# TriMod_Adapter_CPLD_Version.net
KiCad netlist of a schematic drawn in Altium Designer
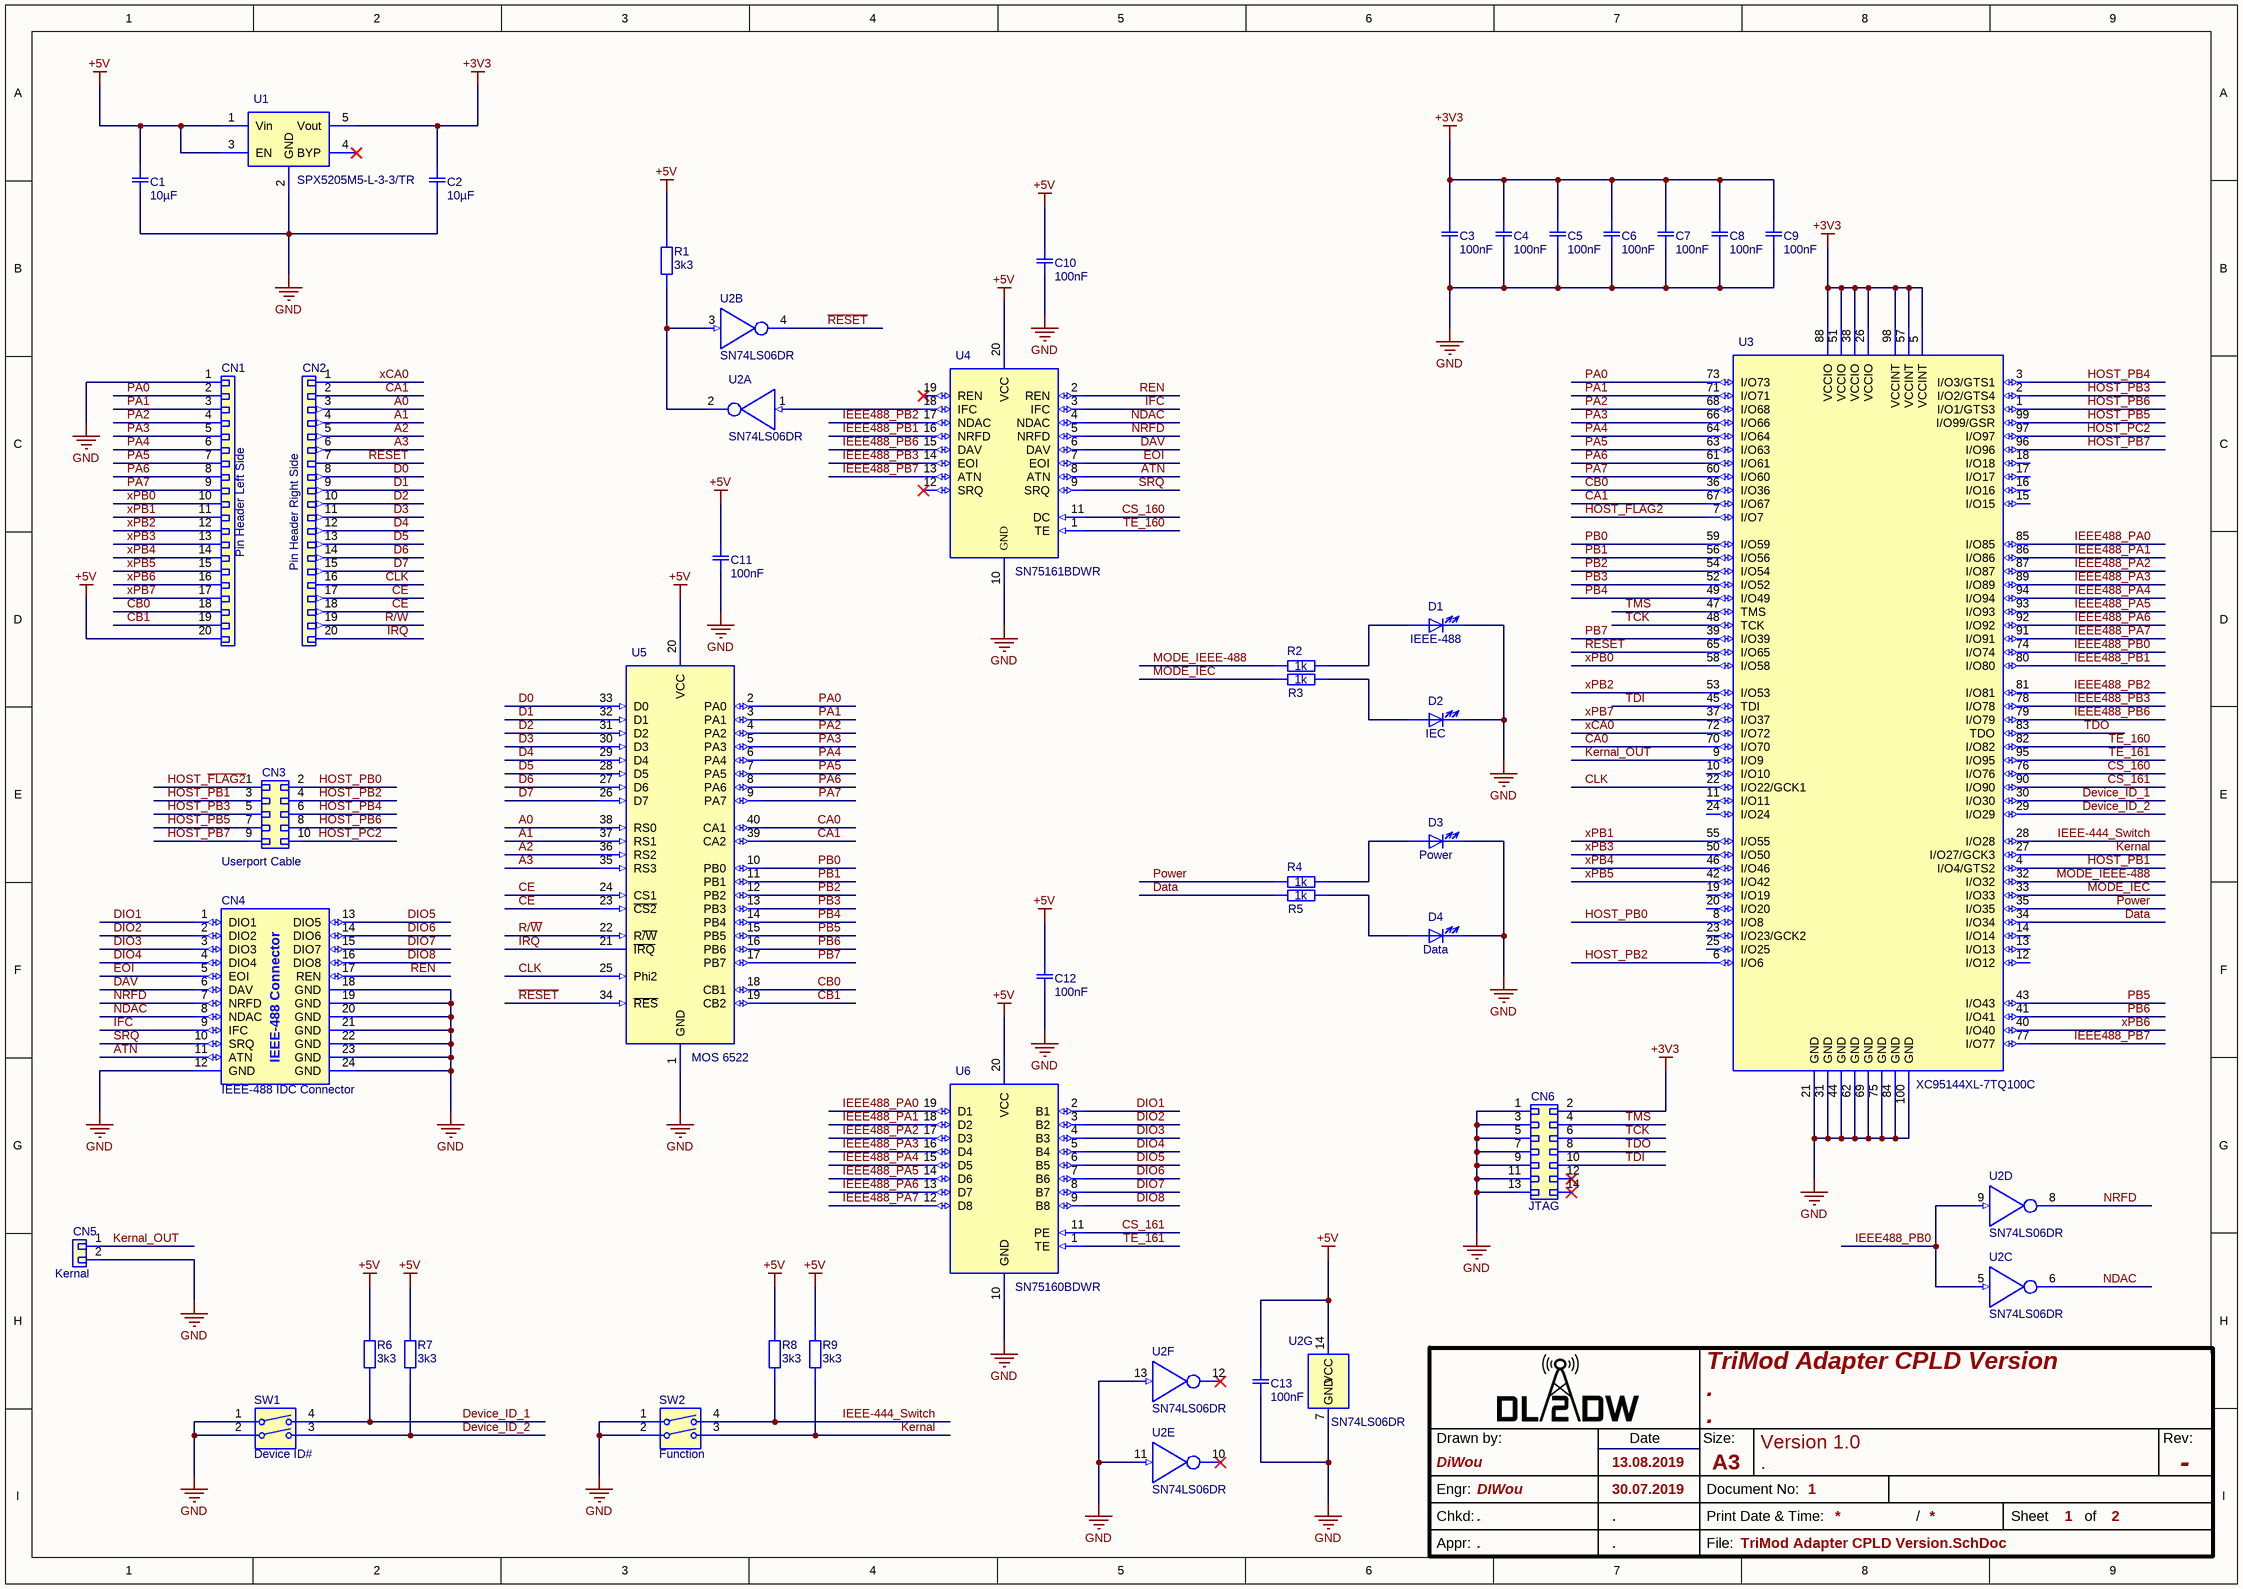
[diagram p0: TriMod Adapter CPLD Version.SchDoc]

(export (version "E")
  (design (tool "Eeschema 10.0.6"))
  (components
    (comp (ref "C1")
      (value "10µF")
      (footprint "Kemet C0805CxxxK8RACTU Series H=1.4mm")
      (description "KEMET - C0805C106K8RACTU - CAP, 10µF, 10V, 10%, X7R, 0805")
      (fields (field (name "VOLTAGE") "10V") (field (name "TOLERANCE") "10%"))
      (libsource (lib "PCB-Tech Cloud") (part "Capacitor"))
    )
    (comp (ref "C2")
      (value "10µF")
      (footprint "Kemet C0805CxxxK8RACTU Series H=1.4mm")
      (description "KEMET - C0805C106K8RACTU - CAP, 10µF, 10V, 10%, X7R, 0805")
      (fields (field (name "VOLTAGE") "10V") (field (name "TOLERANCE") "10%"))
      (libsource (lib "PCB-Tech Cloud") (part "Capacitor"))
    )
    (comp (ref "C3")
      (value "100nF")
      (footprint "CAP 100nF SMD 0603 C0603C104J3RACTU")
      (fields (field (name "TOLERANCE") "5%") (field (name "VOLTAGE") "25V"))
      (libsource (lib "PCB-Tech Cloud") (part "Capacitor"))
    )
    (comp (ref "C4")
      (value "100nF")
      (footprint "CAP 100nF SMD 0603 C0603C104J3RACTU")
      (fields (field (name "TOLERANCE") "5%") (field (name "VOLTAGE") "25V"))
      (libsource (lib "PCB-Tech Cloud") (part "Capacitor"))
    )
    (comp (ref "C5")
      (value "100nF")
      (footprint "CAP 100nF SMD 0603 C0603C104J3RACTU")
      (fields (field (name "TOLERANCE") "5%") (field (name "VOLTAGE") "25V"))
      (libsource (lib "PCB-Tech Cloud") (part "Capacitor"))
    )
    (comp (ref "C6")
      (value "100nF")
      (footprint "CAP 100nF SMD 0603 C0603C104J3RACTU")
      (fields (field (name "TOLERANCE") "5%") (field (name "VOLTAGE") "25V"))
      (libsource (lib "PCB-Tech Cloud") (part "Capacitor"))
    )
    (comp (ref "C7")
      (value "100nF")
      (footprint "CAP 100nF SMD 0603 C0603C104J3RACTU")
      (fields (field (name "TOLERANCE") "5%") (field (name "VOLTAGE") "25V"))
      (libsource (lib "PCB-Tech Cloud") (part "Capacitor"))
    )
    (comp (ref "C8")
      (value "100nF")
      (footprint "CAP 100nF SMD 0603 C0603C104J3RACTU")
      (fields (field (name "TOLERANCE") "5%") (field (name "VOLTAGE") "25V"))
      (libsource (lib "PCB-Tech Cloud") (part "Capacitor"))
    )
    (comp (ref "C9")
      (value "100nF")
      (footprint "CAP 100nF SMD 0603 C0603C104J3RACTU")
      (fields (field (name "TOLERANCE") "5%") (field (name "VOLTAGE") "25V"))
      (libsource (lib "PCB-Tech Cloud") (part "Capacitor"))
    )
    (comp (ref "C10")
      (value "100nF")
      (footprint "CAP 100nF SMD 0603 C0603C104J3RACTU")
      (fields (field (name "TOLERANCE") "5%") (field (name "VOLTAGE") "25V"))
      (libsource (lib "PCB-Tech Cloud") (part "Capacitor"))
    )
    (comp (ref "C11")
      (value "100nF")
      (footprint "CAP 100nF SMD 0603 C0603C104J3RACTU")
      (fields (field (name "TOLERANCE") "5%") (field (name "VOLTAGE") "25V"))
      (libsource (lib "PCB-Tech Cloud") (part "Capacitor"))
    )
    (comp (ref "C12")
      (value "100nF")
      (footprint "CAP 100nF SMD 0603 C0603C104J3RACTU")
      (fields (field (name "TOLERANCE") "5%") (field (name "VOLTAGE") "25V"))
      (libsource (lib "PCB-Tech Cloud") (part "Capacitor"))
    )
    (comp (ref "C13")
      (value "100nF")
      (footprint "CAP 100nF SMD 0603 C0603C104J3RACTU")
      (fields (field (name "TOLERANCE") "5%") (field (name "VOLTAGE") "25V"))
      (libsource (lib "PCB-Tech Cloud") (part "Capacitor"))
    )
    (comp (ref "CN1")
      (value "Pin Header Left Side")
      (footprint "Pin Header 01x20 2.54mm Horizontal Male")
      (description "CONN HEADER .100 SNGL STR 20POS")
      (libsource (lib "PCB-Tech Cloud") (part "CONN 01x20"))
    )
    (comp (ref "CN2")
      (value "Pin Header Right Side")
      (footprint "Pin Header 01x20 2.54mm Horizontal Male")
      (description "CONN HEADER .100 SNGL STR 20POS")
      (libsource (lib "") (part "CONN 01x20_1"))
    )
    (comp (ref "CN3")
      (value "Userport Cable")
      (footprint "IDC Header 2x5 P2.54mm Right Angle")
      (description "Conn Shrouded Header HDR 10 POS 2.54mm Solder RA Thru-Hole Tube")
      (libsource (lib "PCB-Tech Cloud") (part "CONN 02x05 Odd Even"))
    )
    (comp (ref "CN4")
      (value "IEEE-488 IDC Connector")
      (footprint "IEEE-488 IDC Header 2x12 P2.54mm Right Angle")
      (description "IEEE-488 IDC Connector Right Angle or Straight")
      (libsource (lib "PCB-Tech Cloud") (part "IEEE-488 Connector"))
    )
    (comp (ref "CN5")
      (value "Kernal")
      (footprint "Pin Header 01x02 Right Angle RM2.54mm L5.08mm")
      (description "CONN HEADER R/A 2POS 2.54MM")
      (libsource (lib "PCB-Tech Cloud") (part "CONN 01x02"))
    )
    (comp (ref "CN6")
      (value "JTAG")
      (footprint "IDC Header 2x7 P2.54mm Straight")
      (description "Conn Shrouded Header HDR 14 POS 2.54mm Solder ST Thru-Hole")
      (libsource (lib "PCB-Tech Cloud") (part "CONN 02x07 Odd Even"))
    )
    (comp (ref "D1")
      (value "IEEE-488")
      (footprint "LED Blue SMD 0603")
      (description "LED BLUE DIFFUSED 0603 SMD")
      (libsource (lib "PCB-Tech Cloud") (part "LED Standard"))
    )
    (comp (ref "D2")
      (value "IEC")
      (footprint "LED Green SMD 0603")
      (description "LED BLUE DIFFUSED 0603 SMD")
      (libsource (lib "PCB-Tech Cloud") (part "LED Standard"))
    )
    (comp (ref "D3")
      (value "Power")
      (footprint "LED Red SMD 0603")
      (description "LED RED DIFFUSED 0603 SMD")
      (libsource (lib "PCB-Tech Cloud") (part "LED Standard"))
    )
    (comp (ref "D4")
      (value "Data")
      (footprint "LED Yellow SMD 0603")
      (description "LED YELLOW DIFFUSED 0603 SMD")
      (libsource (lib "PCB-Tech Cloud") (part "LED Standard"))
    )
    (comp (ref "R1")
      (value "3k3")
      (footprint "3,3 kOhm R 0805 SMD")
      (description "RES SMD 3.3K OHM 1% 1/8W 0805")
      (fields (field (name "TOLERANCE") "1%"))
      (libsource (lib "PCB-Tech Cloud") (part "Resistor"))
    )
    (comp (ref "R2")
      (value "1k")
      (footprint "1,0 kOhm R 0805 SMD")
      (description "RES SMD 1K OHM 1% 1/8W 0805")
      (fields (field (name "TOLERANCE") "1%"))
      (libsource (lib "PCB-Tech Cloud") (part "Resistor"))
    )
    (comp (ref "R3")
      (value "1k")
      (footprint "1,0 kOhm R 0805 SMD")
      (description "RES SMD 1K OHM 1% 1/8W 0805")
      (fields (field (name "TOLERANCE") "1%"))
      (libsource (lib "PCB-Tech Cloud") (part "Resistor"))
    )
    (comp (ref "R4")
      (value "1k")
      (footprint "1,0 kOhm R 0805 SMD")
      (description "RES SMD 1K OHM 1% 1/8W 0805")
      (fields (field (name "TOLERANCE") "1%"))
      (libsource (lib "PCB-Tech Cloud") (part "Resistor"))
    )
    (comp (ref "R5")
      (value "1k")
      (footprint "1,0 kOhm R 0805 SMD")
      (description "RES SMD 1K OHM 1% 1/8W 0805")
      (fields (field (name "TOLERANCE") "1%"))
      (libsource (lib "PCB-Tech Cloud") (part "Resistor"))
    )
    (comp (ref "R6")
      (value "3k3")
      (footprint "3,3 kOhm R 0805 SMD")
      (description "RES SMD 3.3K OHM 1% 1/8W 0805")
      (fields (field (name "TOLERANCE") "1%"))
      (libsource (lib "PCB-Tech Cloud") (part "Resistor"))
    )
    (comp (ref "R7")
      (value "3k3")
      (footprint "3,3 kOhm R 0805 SMD")
      (description "RES SMD 3.3K OHM 1% 1/8W 0805")
      (fields (field (name "TOLERANCE") "1%"))
      (libsource (lib "PCB-Tech Cloud") (part "Resistor"))
    )
    (comp (ref "R8")
      (value "3k3")
      (footprint "3,3 kOhm R 0805 SMD")
      (description "RES SMD 3.3K OHM 1% 1/8W 0805")
      (fields (field (name "TOLERANCE") "1%"))
      (libsource (lib "PCB-Tech Cloud") (part "Resistor"))
    )
    (comp (ref "R9")
      (value "3k3")
      (footprint "3,3 kOhm R 0805 SMD")
      (description "RES SMD 3.3K OHM 1% 1/8W 0805")
      (fields (field (name "TOLERANCE") "1%"))
      (libsource (lib "PCB-Tech Cloud") (part "Resistor"))
    )
    (comp (ref "SW1")
      (value "Device ID#")
      (footprint "DIP Switch x02")
      (description "SWITCH SLIDE DIP SPST 25MA 24V")
      (libsource (lib "PCB-Tech Cloud") (part "DIP Switch x2"))
    )
    (comp (ref "SW2")
      (value "Function")
      (footprint "DIP Switch x02")
      (description "SWITCH SLIDE DIP SPST 25MA 24V")
      (libsource (lib "PCB-Tech Cloud") (part "DIP Switch x2"))
    )
    (comp (ref "U1")
      (value "SPX5205M5-L-3-3/TR")
      (footprint "SOT-23-5")
      (description "LDO Regulator Pos 3.3V 0.15A 5-Pin SOT-23 T/R")
      (libsource (lib "PCB-Tech Cloud") (part "SPX5205M5-L-3-3/TR"))
    )
    (comp (ref "U2")
      (value "SN74LS06DR")
      (footprint "SN74LS06DR SOIC-14 P1.27mm W3.9mm")
      (description "IC INVERTER OPEN COL 6CH 14SOIC")
      (libsource (lib "") (part "74xx06_1"))
    )
    (comp (ref "U3")
      (value "XC95144XL-7TQ100C")
      (footprint "TQFP-100 P0.5mm XC95144XL-7TQ100C")
      (description "IC CPLD 144MC 7.5NS 100TQFP")
      (libsource (lib "PCB-Tech Cloud") (part "XC95144XL-TQG100C"))
    )
    (comp (ref "U4")
      (value "SN75161BDWR")
      (footprint "SN75161BDWR SOIC-20 W7.5mm P1,27mm")
      (description "TEXAS INSTRUMENTS         SN75161BDWR")
      (libsource (lib "PCB-Tech Cloud") (part "SN75161B"))
    )
    (comp (ref "U5")
      (value "MOS 6522")
      (footprint "MOS 6522 with Socket")
      (description "I/O Controller Interface IC Versatile Interface Adapter")
      (libsource (lib "PCB-Tech Cloud") (part "MOS 6522"))
    )
    (comp (ref "U6")
      (value "SN75160BDWR")
      (footprint "SN75160BDWR SOIC-20 W7.5mm P1,27mm")
      (description "TEXAS INSTRUMENTS         SN75160BDWR.            GENERAL-PURPOSE INTERFACE BUS  ((NW))")
      (libsource (lib "PCB-Tech Cloud") (part "SN75160B"))
    )
  )
  (nets
    (net (code "1") (name "+3V3") (class "Default")
      (node (ref "C2") (pin "2") (pinfunction "2_2") (pintype "passive"))
      (node (ref "C3") (pin "2") (pinfunction "2_2") (pintype "passive"))
      (node (ref "C4") (pin "2") (pinfunction "2_2") (pintype "passive"))
      (node (ref "C5") (pin "2") (pinfunction "2_2") (pintype "passive"))
      (node (ref "C6") (pin "2") (pinfunction "2_2") (pintype "passive"))
      (node (ref "C7") (pin "2") (pinfunction "2_2") (pintype "passive"))
      (node (ref "C8") (pin "2") (pinfunction "2_2") (pintype "passive"))
      (node (ref "C9") (pin "2") (pinfunction "2_2") (pintype "passive"))
      (node (ref "CN6") (pin "2") (pinfunction "2_2") (pintype "passive"))
      (node (ref "U1") (pin "5") (pinfunction "Vout_5") (pintype "power_in"))
      (node (ref "U3") (pin "26") (pinfunction "VCCIO_26") (pintype "power_in"))
      (node (ref "U3") (pin "38") (pinfunction "VCCIO_38") (pintype "power_in"))
      (node (ref "U3") (pin "5") (pinfunction "VCCINT_5") (pintype "power_in"))
      (node (ref "U3") (pin "51") (pinfunction "VCCIO_51") (pintype "power_in"))
      (node (ref "U3") (pin "57") (pinfunction "VCCINT_57") (pintype "power_in"))
      (node (ref "U3") (pin "88") (pinfunction "VCCIO_88") (pintype "power_in"))
      (node (ref "U3") (pin "98") (pinfunction "VCCINT_98") (pintype "power_in"))
    )
    (net (code "2") (name "+5V") (class "Default")
      (node (ref "C1") (pin "2") (pinfunction "2_2") (pintype "passive"))
      (node (ref "C10") (pin "2") (pinfunction "2_2") (pintype "passive"))
      (node (ref "C11") (pin "2") (pinfunction "2_2") (pintype "passive"))
      (node (ref "C12") (pin "2") (pinfunction "2_2") (pintype "passive"))
      (node (ref "C13") (pin "2") (pinfunction "2_2") (pintype "passive"))
      (node (ref "CN1") (pin "20") (pinfunction "20_20") (pintype "passive"))
      (node (ref "R1") (pin "2") (pinfunction "2_2") (pintype "passive"))
      (node (ref "R6") (pin "2") (pinfunction "2_2") (pintype "passive"))
      (node (ref "R7") (pin "2") (pinfunction "2_2") (pintype "passive"))
      (node (ref "R8") (pin "2") (pinfunction "2_2") (pintype "passive"))
      (node (ref "R9") (pin "2") (pinfunction "2_2") (pintype "passive"))
      (node (ref "U1") (pin "1") (pinfunction "Vin_1") (pintype "power_in"))
      (node (ref "U1") (pin "3") (pinfunction "EN_3") (pintype "passive"))
      (node (ref "U2") (pin "14") (pinfunction "VCC_14") (pintype "power_in"))
      (node (ref "U4") (pin "20") (pinfunction "VCC_20") (pintype "power_in"))
      (node (ref "U5") (pin "20") (pinfunction "VCC_20") (pintype "power_in"))
      (node (ref "U6") (pin "20") (pinfunction "VCC_20") (pintype "power_in"))
    )
    (net (code "3") (name "/A0") (class "Default")
      (node (ref "CN2") (pin "3") (pinfunction "3_3") (pintype "output"))
      (node (ref "U5") (pin "38") (pinfunction "RS0_38") (pintype "input"))
    )
    (net (code "4") (name "/A1") (class "Default")
      (node (ref "CN2") (pin "4") (pinfunction "4_4") (pintype "output"))
      (node (ref "U5") (pin "37") (pinfunction "RS1_37") (pintype "input"))
    )
    (net (code "5") (name "/A2") (class "Default")
      (node (ref "CN2") (pin "5") (pinfunction "5_5") (pintype "output"))
      (node (ref "U5") (pin "36") (pinfunction "RS2_36") (pintype "input"))
    )
    (net (code "6") (name "/A3") (class "Default")
      (node (ref "CN2") (pin "6") (pinfunction "6_6") (pintype "output"))
      (node (ref "U5") (pin "35") (pinfunction "RS3_35") (pintype "input"))
    )
    (net (code "7") (name "/ATN") (class "Default")
      (node (ref "CN4") (pin "11") (pinfunction "ATN_11") (pintype "bidirectional"))
      (node (ref "U4") (pin "8") (pinfunction "ATN_8") (pintype "bidirectional"))
    )
    (net (code "8") (name "/CA0") (class "Default")
      (node (ref "U3") (pin "70") (pinfunction "I/O70_70") (pintype "bidirectional"))
      (node (ref "U5") (pin "40") (pinfunction "CA1_40") (pintype "bidirectional"))
    )
    (net (code "9") (name "/CA1") (class "Default")
      (node (ref "CN2") (pin "2") (pinfunction "2_2") (pintype "passive"))
      (node (ref "U3") (pin "67") (pinfunction "I/O67_67") (pintype "bidirectional"))
      (node (ref "U5") (pin "39") (pinfunction "CA2_39") (pintype "bidirectional"))
    )
    (net (code "10") (name "/CB0") (class "Default")
      (node (ref "CN1") (pin "18") (pinfunction "18_18") (pintype "passive"))
      (node (ref "U3") (pin "36") (pinfunction "I/O36_36") (pintype "bidirectional"))
      (node (ref "U5") (pin "18") (pinfunction "CB1_18") (pintype "bidirectional"))
    )
    (net (code "11") (name "/CB1") (class "Default")
      (node (ref "CN1") (pin "19") (pinfunction "19_19") (pintype "passive"))
      (node (ref "U5") (pin "19") (pinfunction "CB2_19") (pintype "bidirectional"))
    )
    (net (code "12") (name "/CE") (class "Default")
      (node (ref "CN2") (pin "17") (pinfunction "17_17") (pintype "output"))
      (node (ref "U5") (pin "24") (pinfunction "CS1_24") (pintype "input"))
    )
    (net (code "13") (name "/CLK") (class "Default")
      (node (ref "CN2") (pin "16") (pinfunction "16_16") (pintype "passive"))
      (node (ref "U3") (pin "22") (pinfunction "I/O22/GCK1_22") (pintype "bidirectional"))
      (node (ref "U5") (pin "25") (pinfunction "Phi2_25") (pintype "input"))
    )
    (net (code "14") (name "/CS_160") (class "Default")
      (node (ref "U3") (pin "76") (pinfunction "I/O76_76") (pintype "bidirectional"))
      (node (ref "U4") (pin "11") (pinfunction "DC_11") (pintype "input"))
    )
    (net (code "15") (name "/CS_161") (class "Default")
      (node (ref "U3") (pin "90") (pinfunction "I/O90_90") (pintype "bidirectional"))
      (node (ref "U6") (pin "11") (pinfunction "PE_11") (pintype "input"))
    )
    (net (code "16") (name "/D0") (class "Default")
      (node (ref "CN2") (pin "8") (pinfunction "8_8") (pintype "output"))
      (node (ref "U5") (pin "33") (pinfunction "D0_33") (pintype "input"))
    )
    (net (code "17") (name "/D1") (class "Default")
      (node (ref "CN2") (pin "9") (pinfunction "9_9") (pintype "output"))
      (node (ref "U5") (pin "32") (pinfunction "D1_32") (pintype "input"))
    )
    (net (code "18") (name "/D2") (class "Default")
      (node (ref "CN2") (pin "10") (pinfunction "10_10") (pintype "output"))
      (node (ref "U5") (pin "31") (pinfunction "D2_31") (pintype "input"))
    )
    (net (code "19") (name "/D3") (class "Default")
      (node (ref "CN2") (pin "11") (pinfunction "11_11") (pintype "output"))
      (node (ref "U5") (pin "30") (pinfunction "D3_30") (pintype "input"))
    )
    (net (code "20") (name "/D4") (class "Default")
      (node (ref "CN2") (pin "12") (pinfunction "12_12") (pintype "output"))
      (node (ref "U5") (pin "29") (pinfunction "D4_29") (pintype "input"))
    )
    (net (code "21") (name "/D5") (class "Default")
      (node (ref "CN2") (pin "13") (pinfunction "13_13") (pintype "output"))
      (node (ref "U5") (pin "28") (pinfunction "D5_28") (pintype "input"))
    )
    (net (code "22") (name "/D6") (class "Default")
      (node (ref "CN2") (pin "14") (pinfunction "14_14") (pintype "output"))
      (node (ref "U5") (pin "27") (pinfunction "D6_27") (pintype "input"))
    )
    (net (code "23") (name "/D7") (class "Default")
      (node (ref "CN2") (pin "15") (pinfunction "15_15") (pintype "output"))
      (node (ref "U5") (pin "26") (pinfunction "D7_26") (pintype "input"))
    )
    (net (code "24") (name "/DAV") (class "Default")
      (node (ref "CN4") (pin "6") (pinfunction "DAV_6") (pintype "bidirectional"))
      (node (ref "U4") (pin "6") (pinfunction "DAV_6") (pintype "bidirectional"))
    )
    (net (code "25") (name "/DIO1") (class "Default")
      (node (ref "CN4") (pin "1") (pinfunction "DIO1_1") (pintype "bidirectional"))
      (node (ref "U6") (pin "2") (pinfunction "B1_2") (pintype "bidirectional"))
    )
    (net (code "26") (name "/DIO2") (class "Default")
      (node (ref "CN4") (pin "2") (pinfunction "DIO2_2") (pintype "bidirectional"))
      (node (ref "U6") (pin "3") (pinfunction "B2_3") (pintype "bidirectional"))
    )
    (net (code "27") (name "/DIO3") (class "Default")
      (node (ref "CN4") (pin "3") (pinfunction "DIO3_3") (pintype "bidirectional"))
      (node (ref "U6") (pin "4") (pinfunction "B3_4") (pintype "bidirectional"))
    )
    (net (code "28") (name "/DIO4") (class "Default")
      (node (ref "CN4") (pin "4") (pinfunction "DIO4_4") (pintype "bidirectional"))
      (node (ref "U6") (pin "5") (pinfunction "B4_5") (pintype "bidirectional"))
    )
    (net (code "29") (name "/DIO5") (class "Default")
      (node (ref "CN4") (pin "13") (pinfunction "DIO5_13") (pintype "bidirectional"))
      (node (ref "U6") (pin "6") (pinfunction "B5_6") (pintype "bidirectional"))
    )
    (net (code "30") (name "/DIO6") (class "Default")
      (node (ref "CN4") (pin "14") (pinfunction "DIO6_14") (pintype "bidirectional"))
      (node (ref "U6") (pin "7") (pinfunction "B6_7") (pintype "bidirectional"))
    )
    (net (code "31") (name "/DIO7") (class "Default")
      (node (ref "CN4") (pin "15") (pinfunction "DIO7_15") (pintype "bidirectional"))
      (node (ref "U6") (pin "8") (pinfunction "B7_8") (pintype "bidirectional"))
    )
    (net (code "32") (name "/DIO8") (class "Default")
      (node (ref "CN4") (pin "16") (pinfunction "DIO8_16") (pintype "bidirectional"))
      (node (ref "U6") (pin "9") (pinfunction "B8_9") (pintype "bidirectional"))
    )
    (net (code "33") (name "/Data") (class "Default")
      (node (ref "R5") (pin "1") (pinfunction "1_1") (pintype "passive"))
      (node (ref "U3") (pin "34") (pinfunction "I/O34_34") (pintype "bidirectional"))
    )
    (net (code "34") (name "/Device_ID_1") (class "Default")
      (node (ref "R6") (pin "1") (pinfunction "1_1") (pintype "passive"))
      (node (ref "SW1") (pin "4") (pinfunction "4_4") (pintype "passive"))
      (node (ref "U3") (pin "30") (pinfunction "I/O30_30") (pintype "bidirectional"))
    )
    (net (code "35") (name "/Device_ID_2") (class "Default")
      (node (ref "R7") (pin "1") (pinfunction "1_1") (pintype "passive"))
      (node (ref "SW1") (pin "3") (pinfunction "3_3") (pintype "passive"))
      (node (ref "U3") (pin "29") (pinfunction "I/O29_29") (pintype "bidirectional"))
    )
    (net (code "36") (name "/EOI") (class "Default")
      (node (ref "CN4") (pin "5") (pinfunction "EOI_5") (pintype "bidirectional"))
      (node (ref "U4") (pin "7") (pinfunction "EOI_7") (pintype "bidirectional"))
    )
    (net (code "37") (name "/HOST_PB0") (class "Default")
      (node (ref "CN3") (pin "2") (pinfunction "2_2") (pintype "passive"))
      (node (ref "U3") (pin "8") (pinfunction "I/O8_8") (pintype "bidirectional"))
    )
    (net (code "38") (name "/HOST_PB1") (class "Default")
      (node (ref "CN3") (pin "3") (pinfunction "3_3") (pintype "passive"))
      (node (ref "U3") (pin "4") (pinfunction "I/O4/GTS2_4") (pintype "bidirectional"))
    )
    (net (code "39") (name "/HOST_PB2") (class "Default")
      (node (ref "CN3") (pin "4") (pinfunction "4_4") (pintype "passive"))
      (node (ref "U3") (pin "6") (pinfunction "I/O6_6") (pintype "bidirectional"))
    )
    (net (code "40") (name "/HOST_PB3") (class "Default")
      (node (ref "CN3") (pin "5") (pinfunction "5_5") (pintype "passive"))
      (node (ref "U3") (pin "2") (pinfunction "I/O2/GTS4_2") (pintype "bidirectional"))
    )
    (net (code "41") (name "/HOST_PB4") (class "Default")
      (node (ref "CN3") (pin "6") (pinfunction "6_6") (pintype "passive"))
      (node (ref "U3") (pin "3") (pinfunction "I/O3/GTS1_3") (pintype "bidirectional"))
    )
    (net (code "42") (name "/HOST_PB5") (class "Default")
      (node (ref "CN3") (pin "7") (pinfunction "7_7") (pintype "passive"))
      (node (ref "U3") (pin "99") (pinfunction "I/O99/GSR_99") (pintype "bidirectional"))
    )
    (net (code "43") (name "/HOST_PB6") (class "Default")
      (node (ref "CN3") (pin "8") (pinfunction "8_8") (pintype "passive"))
      (node (ref "U3") (pin "1") (pinfunction "I/O1/GTS3_1") (pintype "bidirectional"))
    )
    (net (code "44") (name "/HOST_PB7") (class "Default")
      (node (ref "CN3") (pin "9") (pinfunction "9_9") (pintype "passive"))
      (node (ref "U3") (pin "96") (pinfunction "I/O96_96") (pintype "bidirectional"))
    )
    (net (code "45") (name "/HOST_~{FLAG2}") (class "Default")
      (node (ref "CN3") (pin "1") (pinfunction "1_1") (pintype "passive"))
      (node (ref "U3") (pin "7") (pinfunction "I/O7_7") (pintype "bidirectional"))
    )
    (net (code "46") (name "/HOST_~{PC2}") (class "Default")
      (node (ref "CN3") (pin "10") (pinfunction "10_10") (pintype "passive"))
      (node (ref "U3") (pin "97") (pinfunction "I/O97_97") (pintype "bidirectional"))
    )
    (net (code "47") (name "/IEEE-444_Switch") (class "Default")
      (node (ref "R8") (pin "1") (pinfunction "1_1") (pintype "passive"))
      (node (ref "SW2") (pin "4") (pinfunction "4_4") (pintype "passive"))
      (node (ref "U3") (pin "28") (pinfunction "I/O28_28") (pintype "bidirectional"))
    )
    (net (code "48") (name "/IEEE488_PA0") (class "Default")
      (node (ref "U3") (pin "85") (pinfunction "I/O85_85") (pintype "bidirectional"))
      (node (ref "U6") (pin "19") (pinfunction "D1_19") (pintype "bidirectional"))
    )
    (net (code "49") (name "/IEEE488_PA1") (class "Default")
      (node (ref "U3") (pin "86") (pinfunction "I/O86_86") (pintype "bidirectional"))
      (node (ref "U6") (pin "18") (pinfunction "D2_18") (pintype "bidirectional"))
    )
    (net (code "50") (name "/IEEE488_PA2") (class "Default")
      (node (ref "U3") (pin "87") (pinfunction "I/O87_87") (pintype "bidirectional"))
      (node (ref "U6") (pin "17") (pinfunction "D3_17") (pintype "bidirectional"))
    )
    (net (code "51") (name "/IEEE488_PA3") (class "Default")
      (node (ref "U3") (pin "89") (pinfunction "I/O89_89") (pintype "bidirectional"))
      (node (ref "U6") (pin "16") (pinfunction "D4_16") (pintype "bidirectional"))
    )
    (net (code "52") (name "/IEEE488_PA4") (class "Default")
      (node (ref "U3") (pin "94") (pinfunction "I/O94_94") (pintype "bidirectional"))
      (node (ref "U6") (pin "15") (pinfunction "D5_15") (pintype "bidirectional"))
    )
    (net (code "53") (name "/IEEE488_PA5") (class "Default")
      (node (ref "U3") (pin "93") (pinfunction "I/O93_93") (pintype "bidirectional"))
      (node (ref "U6") (pin "14") (pinfunction "D6_14") (pintype "bidirectional"))
    )
    (net (code "54") (name "/IEEE488_PA6") (class "Default")
      (node (ref "U3") (pin "92") (pinfunction "I/O92_92") (pintype "bidirectional"))
      (node (ref "U6") (pin "13") (pinfunction "D7_13") (pintype "bidirectional"))
    )
    (net (code "55") (name "/IEEE488_PA7") (class "Default")
      (node (ref "U3") (pin "91") (pinfunction "I/O91_91") (pintype "bidirectional"))
      (node (ref "U6") (pin "12") (pinfunction "D8_12") (pintype "bidirectional"))
    )
    (net (code "56") (name "/IEEE488_PB0") (class "Default")
      (node (ref "U2") (pin "5") (pinfunction "3A_5") (pintype "input"))
      (node (ref "U2") (pin "9") (pinfunction "4A_9") (pintype "input"))
      (node (ref "U3") (pin "74") (pinfunction "I/O74_74") (pintype "bidirectional"))
    )
    (net (code "57") (name "/IEEE488_PB1") (class "Default")
      (node (ref "U3") (pin "80") (pinfunction "I/O80_80") (pintype "bidirectional"))
      (node (ref "U4") (pin "16") (pinfunction "NRFD_16") (pintype "bidirectional"))
    )
    (net (code "58") (name "/IEEE488_PB2") (class "Default")
      (node (ref "U3") (pin "81") (pinfunction "I/O81_81") (pintype "bidirectional"))
      (node (ref "U4") (pin "17") (pinfunction "NDAC_17") (pintype "bidirectional"))
    )
    (net (code "59") (name "/IEEE488_PB3") (class "Default")
      (node (ref "U3") (pin "78") (pinfunction "I/O78_78") (pintype "bidirectional"))
      (node (ref "U4") (pin "14") (pinfunction "EOI_14") (pintype "bidirectional"))
    )
    (net (code "60") (name "/IEEE488_PB6") (class "Default")
      (node (ref "U3") (pin "79") (pinfunction "I/O79_79") (pintype "bidirectional"))
      (node (ref "U4") (pin "15") (pinfunction "DAV_15") (pintype "bidirectional"))
    )
    (net (code "61") (name "/IEEE488_PB7") (class "Default")
      (node (ref "U3") (pin "77") (pinfunction "I/O77_77") (pintype "bidirectional"))
      (node (ref "U4") (pin "13") (pinfunction "ATN_13") (pintype "bidirectional"))
    )
    (net (code "62") (name "/IFC") (class "Default")
      (node (ref "CN4") (pin "9") (pinfunction "IFC_9") (pintype "bidirectional"))
      (node (ref "U4") (pin "3") (pinfunction "IFC_3") (pintype "bidirectional"))
    )
    (net (code "63") (name "/Kernal") (class "Default")
      (node (ref "R9") (pin "1") (pinfunction "1_1") (pintype "passive"))
      (node (ref "SW2") (pin "3") (pinfunction "3_3") (pintype "passive"))
      (node (ref "U3") (pin "27") (pinfunction "I/O27/GCK3_27") (pintype "bidirectional"))
    )
    (net (code "64") (name "/Kernal_OUT") (class "Default")
      (node (ref "CN5") (pin "1") (pinfunction "1_1") (pintype "passive"))
      (node (ref "U3") (pin "9") (pinfunction "I/O9_9") (pintype "bidirectional"))
    )
    (net (code "65") (name "/MODE_IEC") (class "Default")
      (node (ref "R3") (pin "1") (pinfunction "1_1") (pintype "passive"))
      (node (ref "U3") (pin "33") (pinfunction "I/O33_33") (pintype "bidirectional"))
    )
    (net (code "66") (name "/MODE_IEEE-488") (class "Default")
      (node (ref "R2") (pin "1") (pinfunction "1_1") (pintype "passive"))
      (node (ref "U3") (pin "32") (pinfunction "I/O32_32") (pintype "bidirectional"))
    )
    (net (code "67") (name "/NDAC") (class "Default")
      (node (ref "CN4") (pin "8") (pinfunction "NDAC_8") (pintype "bidirectional"))
      (node (ref "U2") (pin "6") (pinfunction "3Y_6") (pintype "open_collector"))
      (node (ref "U4") (pin "4") (pinfunction "NDAC_4") (pintype "bidirectional"))
    )
    (net (code "68") (name "/NRFD") (class "Default")
      (node (ref "CN4") (pin "7") (pinfunction "NRFD_7") (pintype "bidirectional"))
      (node (ref "U2") (pin "8") (pinfunction "4Y_8") (pintype "open_collector"))
      (node (ref "U4") (pin "5") (pinfunction "NRFD_5") (pintype "bidirectional"))
    )
    (net (code "69") (name "/PA0") (class "Default")
      (node (ref "CN1") (pin "2") (pinfunction "2_2") (pintype "passive"))
      (node (ref "U3") (pin "73") (pinfunction "I/O73_73") (pintype "bidirectional"))
      (node (ref "U5") (pin "2") (pinfunction "PA0_2") (pintype "bidirectional"))
    )
    (net (code "70") (name "/PA1") (class "Default")
      (node (ref "CN1") (pin "3") (pinfunction "3_3") (pintype "passive"))
      (node (ref "U3") (pin "71") (pinfunction "I/O71_71") (pintype "bidirectional"))
      (node (ref "U5") (pin "3") (pinfunction "PA1_3") (pintype "bidirectional"))
    )
    (net (code "71") (name "/PA2") (class "Default")
      (node (ref "CN1") (pin "4") (pinfunction "4_4") (pintype "passive"))
      (node (ref "U3") (pin "68") (pinfunction "I/O68_68") (pintype "bidirectional"))
      (node (ref "U5") (pin "4") (pinfunction "PA2_4") (pintype "bidirectional"))
    )
    (net (code "72") (name "/PA3") (class "Default")
      (node (ref "CN1") (pin "5") (pinfunction "5_5") (pintype "passive"))
      (node (ref "U3") (pin "66") (pinfunction "I/O66_66") (pintype "bidirectional"))
      (node (ref "U5") (pin "5") (pinfunction "PA3_5") (pintype "bidirectional"))
    )
    (net (code "73") (name "/PA4") (class "Default")
      (node (ref "CN1") (pin "6") (pinfunction "6_6") (pintype "passive"))
      (node (ref "U3") (pin "64") (pinfunction "I/O64_64") (pintype "bidirectional"))
      (node (ref "U5") (pin "6") (pinfunction "PA4_6") (pintype "bidirectional"))
    )
    (net (code "74") (name "/PA5") (class "Default")
      (node (ref "CN1") (pin "7") (pinfunction "7_7") (pintype "passive"))
      (node (ref "U3") (pin "63") (pinfunction "I/O63_63") (pintype "bidirectional"))
      (node (ref "U5") (pin "7") (pinfunction "PA5_7") (pintype "bidirectional"))
    )
    (net (code "75") (name "/PA6") (class "Default")
      (node (ref "CN1") (pin "8") (pinfunction "8_8") (pintype "passive"))
      (node (ref "U3") (pin "61") (pinfunction "I/O61_61") (pintype "bidirectional"))
      (node (ref "U5") (pin "8") (pinfunction "PA6_8") (pintype "bidirectional"))
    )
    (net (code "76") (name "/PA7") (class "Default")
      (node (ref "CN1") (pin "9") (pinfunction "9_9") (pintype "passive"))
      (node (ref "U3") (pin "60") (pinfunction "I/O60_60") (pintype "bidirectional"))
      (node (ref "U5") (pin "9") (pinfunction "PA7_9") (pintype "bidirectional"))
    )
    (net (code "77") (name "/PB0") (class "Default")
      (node (ref "U3") (pin "59") (pinfunction "I/O59_59") (pintype "bidirectional"))
      (node (ref "U5") (pin "10") (pinfunction "PB0_10") (pintype "bidirectional"))
    )
    (net (code "78") (name "/PB1") (class "Default")
      (node (ref "U3") (pin "56") (pinfunction "I/O56_56") (pintype "bidirectional"))
      (node (ref "U5") (pin "11") (pinfunction "PB1_11") (pintype "bidirectional"))
    )
    (net (code "79") (name "/PB2") (class "Default")
      (node (ref "U3") (pin "54") (pinfunction "I/O54_54") (pintype "bidirectional"))
      (node (ref "U5") (pin "12") (pinfunction "PB2_12") (pintype "bidirectional"))
    )
    (net (code "80") (name "/PB3") (class "Default")
      (node (ref "U3") (pin "52") (pinfunction "I/O52_52") (pintype "bidirectional"))
      (node (ref "U5") (pin "13") (pinfunction "PB3_13") (pintype "bidirectional"))
    )
    (net (code "81") (name "/PB4") (class "Default")
      (node (ref "U3") (pin "49") (pinfunction "I/O49_49") (pintype "bidirectional"))
      (node (ref "U5") (pin "14") (pinfunction "PB4_14") (pintype "bidirectional"))
    )
    (net (code "82") (name "/PB5") (class "Default")
      (node (ref "U3") (pin "43") (pinfunction "I/O43_43") (pintype "bidirectional"))
      (node (ref "U5") (pin "15") (pinfunction "PB5_15") (pintype "bidirectional"))
    )
    (net (code "83") (name "/PB6") (class "Default")
      (node (ref "U3") (pin "41") (pinfunction "I/O41_41") (pintype "bidirectional"))
      (node (ref "U5") (pin "16") (pinfunction "PB6_16") (pintype "bidirectional"))
    )
    (net (code "84") (name "/PB7") (class "Default")
      (node (ref "U3") (pin "39") (pinfunction "I/O39_39") (pintype "bidirectional"))
      (node (ref "U5") (pin "17") (pinfunction "PB7_17") (pintype "bidirectional"))
    )
    (net (code "85") (name "/Power") (class "Default")
      (node (ref "R4") (pin "1") (pinfunction "1_1") (pintype "passive"))
      (node (ref "U3") (pin "35") (pinfunction "I/O35_35") (pintype "bidirectional"))
    )
    (net (code "86") (name "/REN") (class "Default")
      (node (ref "CN4") (pin "17") (pinfunction "REN_17") (pintype "bidirectional"))
      (node (ref "U4") (pin "2") (pinfunction "REN_2") (pintype "bidirectional"))
    )
    (net (code "87") (name "/R{slash}~{W}") (class "Default")
      (node (ref "CN2") (pin "19") (pinfunction "19_19") (pintype "output"))
      (node (ref "U5") (pin "22") (pinfunction "R~{/W}_22") (pintype "input"))
    )
    (net (code "88") (name "/SRQ") (class "Default")
      (node (ref "CN4") (pin "10") (pinfunction "SRQ_10") (pintype "bidirectional"))
      (node (ref "U4") (pin "9") (pinfunction "SRQ_9") (pintype "bidirectional"))
    )
    (net (code "89") (name "/TCK") (class "Default")
      (node (ref "CN6") (pin "6") (pinfunction "6_6") (pintype "passive"))
      (node (ref "U3") (pin "48") (pinfunction "TCK_48") (pintype "bidirectional"))
    )
    (net (code "90") (name "/TDI") (class "Default")
      (node (ref "CN6") (pin "10") (pinfunction "10_10") (pintype "passive"))
      (node (ref "U3") (pin "45") (pinfunction "TDI_45") (pintype "bidirectional"))
    )
    (net (code "91") (name "/TDO") (class "Default")
      (node (ref "CN6") (pin "8") (pinfunction "8_8") (pintype "passive"))
      (node (ref "U3") (pin "83") (pinfunction "TDO_83") (pintype "bidirectional"))
    )
    (net (code "92") (name "/TE_160") (class "Default")
      (node (ref "U3") (pin "82") (pinfunction "I/O82_82") (pintype "bidirectional"))
      (node (ref "U4") (pin "1") (pinfunction "TE_1") (pintype "input"))
    )
    (net (code "93") (name "/TE_161") (class "Default")
      (node (ref "U3") (pin "95") (pinfunction "I/O95_95") (pintype "bidirectional"))
      (node (ref "U6") (pin "1") (pinfunction "TE_1") (pintype "input"))
    )
    (net (code "94") (name "/TMS") (class "Default")
      (node (ref "CN6") (pin "4") (pinfunction "4_4") (pintype "passive"))
      (node (ref "U3") (pin "47") (pinfunction "TMS_47") (pintype "bidirectional"))
    )
    (net (code "95") (name "/xCA0") (class "Default")
      (node (ref "CN2") (pin "1") (pinfunction "1_1") (pintype "passive"))
      (node (ref "U3") (pin "72") (pinfunction "I/O72_72") (pintype "bidirectional"))
    )
    (net (code "96") (name "/xPB0") (class "Default")
      (node (ref "CN1") (pin "10") (pinfunction "10_10") (pintype "passive"))
      (node (ref "U3") (pin "58") (pinfunction "I/O58_58") (pintype "bidirectional"))
    )
    (net (code "97") (name "/xPB1") (class "Default")
      (node (ref "CN1") (pin "11") (pinfunction "11_11") (pintype "passive"))
      (node (ref "U3") (pin "55") (pinfunction "I/O55_55") (pintype "bidirectional"))
    )
    (net (code "98") (name "/xPB2") (class "Default")
      (node (ref "CN1") (pin "12") (pinfunction "12_12") (pintype "passive"))
      (node (ref "U3") (pin "53") (pinfunction "I/O53_53") (pintype "bidirectional"))
    )
    (net (code "99") (name "/xPB3") (class "Default")
      (node (ref "CN1") (pin "13") (pinfunction "13_13") (pintype "passive"))
      (node (ref "U3") (pin "50") (pinfunction "I/O50_50") (pintype "bidirectional"))
    )
    (net (code "100") (name "/xPB4") (class "Default")
      (node (ref "CN1") (pin "14") (pinfunction "14_14") (pintype "passive"))
      (node (ref "U3") (pin "46") (pinfunction "I/O46_46") (pintype "bidirectional"))
    )
    (net (code "101") (name "/xPB5") (class "Default")
      (node (ref "CN1") (pin "15") (pinfunction "15_15") (pintype "passive"))
      (node (ref "U3") (pin "42") (pinfunction "I/O42_42") (pintype "bidirectional"))
    )
    (net (code "102") (name "/xPB6") (class "Default")
      (node (ref "CN1") (pin "16") (pinfunction "16_16") (pintype "passive"))
      (node (ref "U3") (pin "40") (pinfunction "I/O40_40") (pintype "bidirectional"))
    )
    (net (code "103") (name "/xPB7") (class "Default")
      (node (ref "CN1") (pin "17") (pinfunction "17_17") (pintype "passive"))
      (node (ref "U3") (pin "37") (pinfunction "I/O37_37") (pintype "bidirectional"))
    )
    (net (code "104") (name "/~{CE}") (class "Default")
      (node (ref "CN2") (pin "18") (pinfunction "18_18") (pintype "output"))
      (node (ref "U5") (pin "23") (pinfunction "~{CS2}_23") (pintype "input"))
    )
    (net (code "105") (name "/~{IRQ}") (class "Default")
      (node (ref "CN2") (pin "20") (pinfunction "20_20") (pintype "passive"))
      (node (ref "U5") (pin "21") (pinfunction "~{IRQ}_21") (pintype "open_collector"))
    )
    (net (code "106") (name "/~{RESET}") (class "Default")
      (node (ref "CN2") (pin "7") (pinfunction "7_7") (pintype "passive"))
      (node (ref "U2") (pin "4") (pinfunction "2Y_4") (pintype "open_collector"))
      (node (ref "U3") (pin "65") (pinfunction "I/O65_65") (pintype "bidirectional"))
      (node (ref "U5") (pin "34") (pinfunction "~{RES}_34") (pintype "input"))
    )
    (net (code "107") (name "GND") (class "Default")
      (node (ref "C1") (pin "1") (pinfunction "1_1") (pintype "passive"))
      (node (ref "C10") (pin "1") (pinfunction "1_1") (pintype "passive"))
      (node (ref "C11") (pin "1") (pinfunction "1_1") (pintype "passive"))
      (node (ref "C12") (pin "1") (pinfunction "1_1") (pintype "passive"))
      (node (ref "C13") (pin "1") (pinfunction "1_1") (pintype "passive"))
      (node (ref "C2") (pin "1") (pinfunction "1_1") (pintype "passive"))
      (node (ref "C3") (pin "1") (pinfunction "1_1") (pintype "passive"))
      (node (ref "C4") (pin "1") (pinfunction "1_1") (pintype "passive"))
      (node (ref "C5") (pin "1") (pinfunction "1_1") (pintype "passive"))
      (node (ref "C6") (pin "1") (pinfunction "1_1") (pintype "passive"))
      (node (ref "C7") (pin "1") (pinfunction "1_1") (pintype "passive"))
      (node (ref "C8") (pin "1") (pinfunction "1_1") (pintype "passive"))
      (node (ref "C9") (pin "1") (pinfunction "1_1") (pintype "passive"))
      (node (ref "CN1") (pin "1") (pinfunction "1_1") (pintype "passive"))
      (node (ref "CN4") (pin "12") (pinfunction "GND_12") (pintype "passive"))
      (node (ref "CN4") (pin "18") (pinfunction "GND_18") (pintype "passive"))
      (node (ref "CN4") (pin "19") (pinfunction "GND_19") (pintype "passive"))
      (node (ref "CN4") (pin "20") (pinfunction "GND_20") (pintype "passive"))
      (node (ref "CN4") (pin "21") (pinfunction "GND_21") (pintype "passive"))
      (node (ref "CN4") (pin "22") (pinfunction "GND_22") (pintype "passive"))
      (node (ref "CN4") (pin "23") (pinfunction "GND_23") (pintype "passive"))
      (node (ref "CN4") (pin "24") (pinfunction "GND_24") (pintype "passive"))
      (node (ref "CN5") (pin "2") (pinfunction "2_2") (pintype "passive"))
      (node (ref "CN6") (pin "1") (pinfunction "1_1") (pintype "passive"))
      (node (ref "CN6") (pin "11") (pinfunction "11_11") (pintype "passive"))
      (node (ref "CN6") (pin "13") (pinfunction "13_13") (pintype "passive"))
      (node (ref "CN6") (pin "3") (pinfunction "3_3") (pintype "passive"))
      (node (ref "CN6") (pin "5") (pinfunction "5_5") (pintype "passive"))
      (node (ref "CN6") (pin "7") (pinfunction "7_7") (pintype "passive"))
      (node (ref "CN6") (pin "9") (pinfunction "9_9") (pintype "passive"))
      (node (ref "D1") (pin "1") (pinfunction "1_1") (pintype "passive"))
      (node (ref "D2") (pin "1") (pinfunction "1_1") (pintype "passive"))
      (node (ref "D3") (pin "1") (pinfunction "1_1") (pintype "passive"))
      (node (ref "D4") (pin "1") (pinfunction "1_1") (pintype "passive"))
      (node (ref "SW1") (pin "1") (pinfunction "1_1") (pintype "passive"))
      (node (ref "SW1") (pin "2") (pinfunction "2_2") (pintype "passive"))
      (node (ref "SW2") (pin "1") (pinfunction "1_1") (pintype "passive"))
      (node (ref "SW2") (pin "2") (pinfunction "2_2") (pintype "passive"))
      (node (ref "U1") (pin "2") (pinfunction "GND_2") (pintype "power_in"))
      (node (ref "U2") (pin "11") (pinfunction "5A_11") (pintype "input"))
      (node (ref "U2") (pin "13") (pinfunction "6A_13") (pintype "input"))
      (node (ref "U2") (pin "7") (pinfunction "GND_7") (pintype "passive"))
      (node (ref "U3") (pin "100") (pinfunction "GND_100") (pintype "passive"))
      (node (ref "U3") (pin "21") (pinfunction "GND_21") (pintype "passive"))
      (node (ref "U3") (pin "31") (pinfunction "GND_31") (pintype "passive"))
      (node (ref "U3") (pin "44") (pinfunction "GND_44") (pintype "passive"))
      (node (ref "U3") (pin "62") (pinfunction "GND_62") (pintype "passive"))
      (node (ref "U3") (pin "69") (pinfunction "GND_69") (pintype "passive"))
      (node (ref "U3") (pin "75") (pinfunction "GND_75") (pintype "passive"))
      (node (ref "U3") (pin "84") (pinfunction "GND_84") (pintype "passive"))
      (node (ref "U4") (pin "10") (pinfunction "GND_10") (pintype "power_in"))
      (node (ref "U5") (pin "1") (pinfunction "GND_1") (pintype "passive"))
      (node (ref "U6") (pin "10") (pinfunction "GND_10") (pintype "power_in"))
    )
    (net (code "108") (name "Net-(D1-Pad2)") (class "Default")
      (node (ref "D1") (pin "2") (pinfunction "2_2") (pintype "passive"))
      (node (ref "R2") (pin "2") (pinfunction "2_2") (pintype "passive"))
    )
    (net (code "109") (name "Net-(D2-Pad2)") (class "Default")
      (node (ref "D2") (pin "2") (pinfunction "2_2") (pintype "passive"))
      (node (ref "R3") (pin "2") (pinfunction "2_2") (pintype "passive"))
    )
    (net (code "110") (name "Net-(D3-Pad2)") (class "Default")
      (node (ref "D3") (pin "2") (pinfunction "2_2") (pintype "passive"))
      (node (ref "R4") (pin "2") (pinfunction "2_2") (pintype "passive"))
    )
    (net (code "111") (name "Net-(D4-Pad2)") (class "Default")
      (node (ref "D4") (pin "2") (pinfunction "2_2") (pintype "passive"))
      (node (ref "R5") (pin "2") (pinfunction "2_2") (pintype "passive"))
    )
    (net (code "112") (name "Net-(U2A-1A)") (class "Default")
      (node (ref "U2") (pin "1") (pinfunction "1A_1") (pintype "input"))
      (node (ref "U4") (pin "18") (pinfunction "IFC_18") (pintype "bidirectional"))
    )
    (net (code "113") (name "Net-(U2A-1Y)") (class "Default")
      (node (ref "R1") (pin "1") (pinfunction "1_1") (pintype "passive"))
      (node (ref "U2") (pin "2") (pinfunction "1Y_2") (pintype "open_collector"))
      (node (ref "U2") (pin "3") (pinfunction "2A_3") (pintype "input"))
    )
    (net (code "114") (name "unconnected-(CN6-Pad12)") (class "Default")
      (node (ref "CN6") (pin "12") (pinfunction "12_12") (pintype "passive+no_connect"))
    )
    (net (code "115") (name "unconnected-(CN6-Pad14)") (class "Default")
      (node (ref "CN6") (pin "14") (pinfunction "14_14") (pintype "passive+no_connect"))
    )
    (net (code "116") (name "unconnected-(U1-BYP-Pad4)") (class "Default")
      (node (ref "U1") (pin "4") (pinfunction "BYP_4") (pintype "passive+no_connect"))
    )
    (net (code "117") (name "unconnected-(U2E-5Y-Pad10)") (class "Default")
      (node (ref "U2") (pin "10") (pinfunction "5Y_10") (pintype "open_collector+no_connect"))
    )
    (net (code "118") (name "unconnected-(U2F-6Y-Pad12)") (class "Default")
      (node (ref "U2") (pin "12") (pinfunction "6Y_12") (pintype "open_collector+no_connect"))
    )
    (net (code "119") (name "unconnected-(U3-I{slash}O10-Pad10)") (class "Default")
      (node (ref "U3") (pin "10") (pinfunction "I/O10_10") (pintype "bidirectional"))
    )
    (net (code "120") (name "unconnected-(U3-I{slash}O11-Pad11)") (class "Default")
      (node (ref "U3") (pin "11") (pinfunction "I/O11_11") (pintype "bidirectional"))
    )
    (net (code "121") (name "unconnected-(U3-I{slash}O12-Pad12)") (class "Default")
      (node (ref "U3") (pin "12") (pinfunction "I/O12_12") (pintype "bidirectional"))
    )
    (net (code "122") (name "unconnected-(U3-I{slash}O13-Pad13)") (class "Default")
      (node (ref "U3") (pin "13") (pinfunction "I/O13_13") (pintype "bidirectional"))
    )
    (net (code "123") (name "unconnected-(U3-I{slash}O14-Pad14)") (class "Default")
      (node (ref "U3") (pin "14") (pinfunction "I/O14_14") (pintype "bidirectional"))
    )
    (net (code "124") (name "unconnected-(U3-I{slash}O15-Pad15)") (class "Default")
      (node (ref "U3") (pin "15") (pinfunction "I/O15_15") (pintype "bidirectional"))
    )
    (net (code "125") (name "unconnected-(U3-I{slash}O16-Pad16)") (class "Default")
      (node (ref "U3") (pin "16") (pinfunction "I/O16_16") (pintype "bidirectional"))
    )
    (net (code "126") (name "unconnected-(U3-I{slash}O17-Pad17)") (class "Default")
      (node (ref "U3") (pin "17") (pinfunction "I/O17_17") (pintype "bidirectional"))
    )
    (net (code "127") (name "unconnected-(U3-I{slash}O18-Pad18)") (class "Default")
      (node (ref "U3") (pin "18") (pinfunction "I/O18_18") (pintype "bidirectional"))
    )
    (net (code "128") (name "unconnected-(U3-I{slash}O19-Pad19)") (class "Default")
      (node (ref "U3") (pin "19") (pinfunction "I/O19_19") (pintype "bidirectional"))
    )
    (net (code "129") (name "unconnected-(U3-I{slash}O20-Pad20)") (class "Default")
      (node (ref "U3") (pin "20") (pinfunction "I/O20_20") (pintype "bidirectional"))
    )
    (net (code "130") (name "unconnected-(U3-I{slash}O23{slash}GCK2-Pad23)") (class "Default")
      (node (ref "U3") (pin "23") (pinfunction "I/O23/GCK2_23") (pintype "bidirectional"))
    )
    (net (code "131") (name "unconnected-(U3-I{slash}O24-Pad24)") (class "Default")
      (node (ref "U3") (pin "24") (pinfunction "I/O24_24") (pintype "bidirectional"))
    )
    (net (code "132") (name "unconnected-(U3-I{slash}O25-Pad25)") (class "Default")
      (node (ref "U3") (pin "25") (pinfunction "I/O25_25") (pintype "bidirectional"))
    )
    (net (code "133") (name "unconnected-(U4-REN-Pad19)") (class "Default")
      (node (ref "U4") (pin "19") (pinfunction "REN_19") (pintype "bidirectional+no_connect"))
    )
    (net (code "134") (name "unconnected-(U4-SRQ-Pad12)") (class "Default")
      (node (ref "U4") (pin "12") (pinfunction "SRQ_12") (pintype "bidirectional+no_connect"))
    )
  )
)
